# STM32F103ZET6.net
KiCad netlist of a schematic drawn in Altium Designer
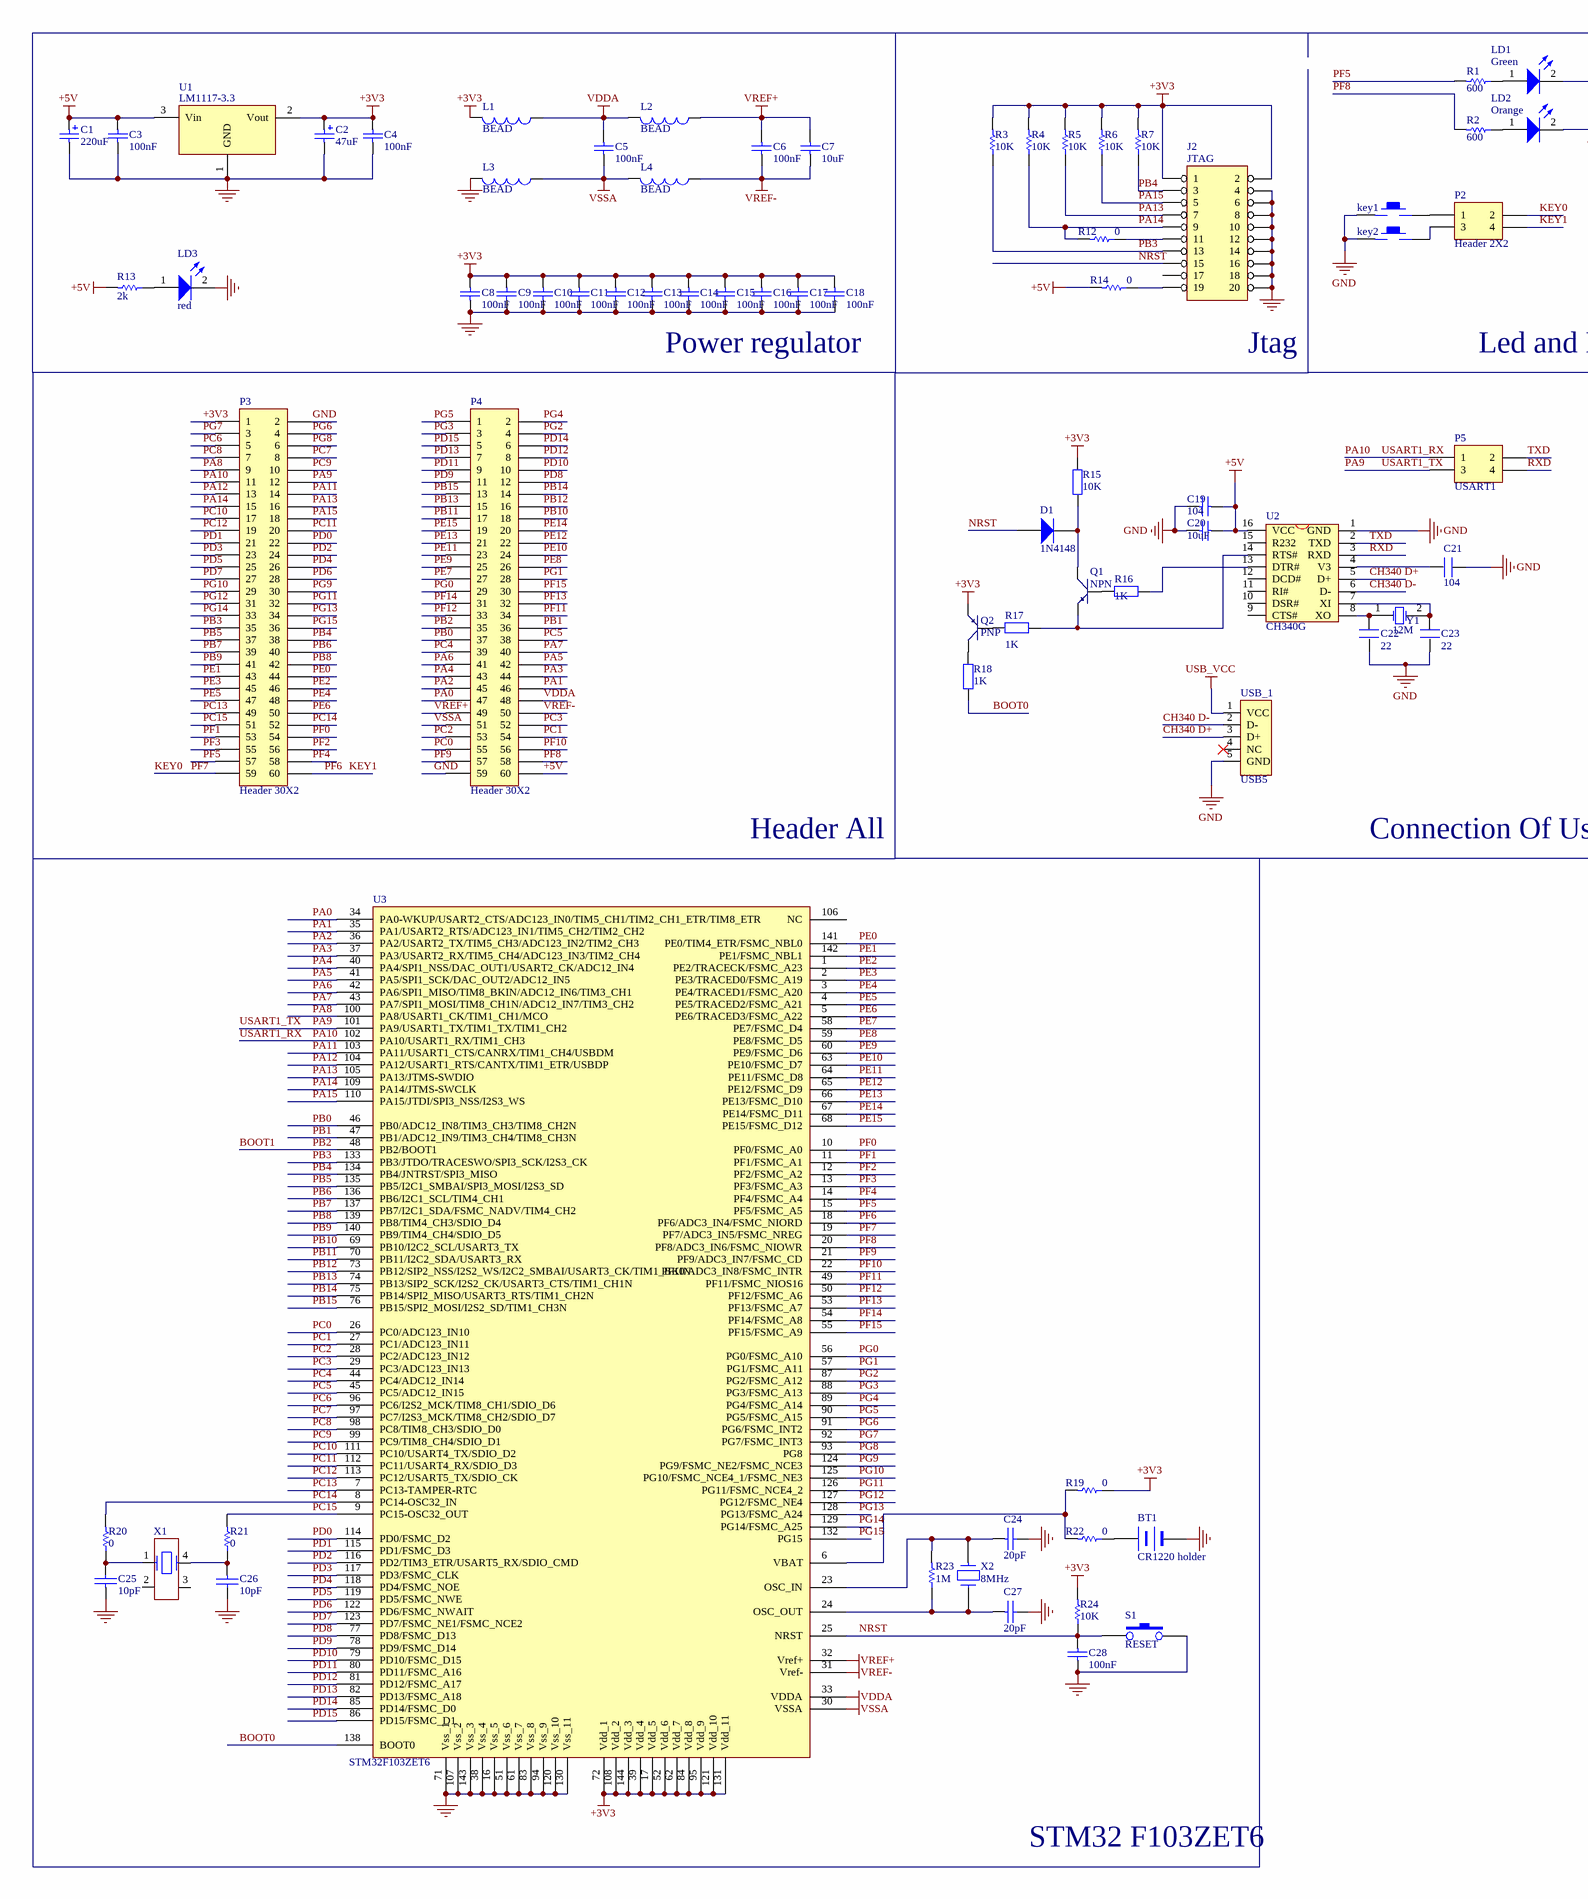
[diagram p0: STM32F103ZET6.SCHDOC, left]
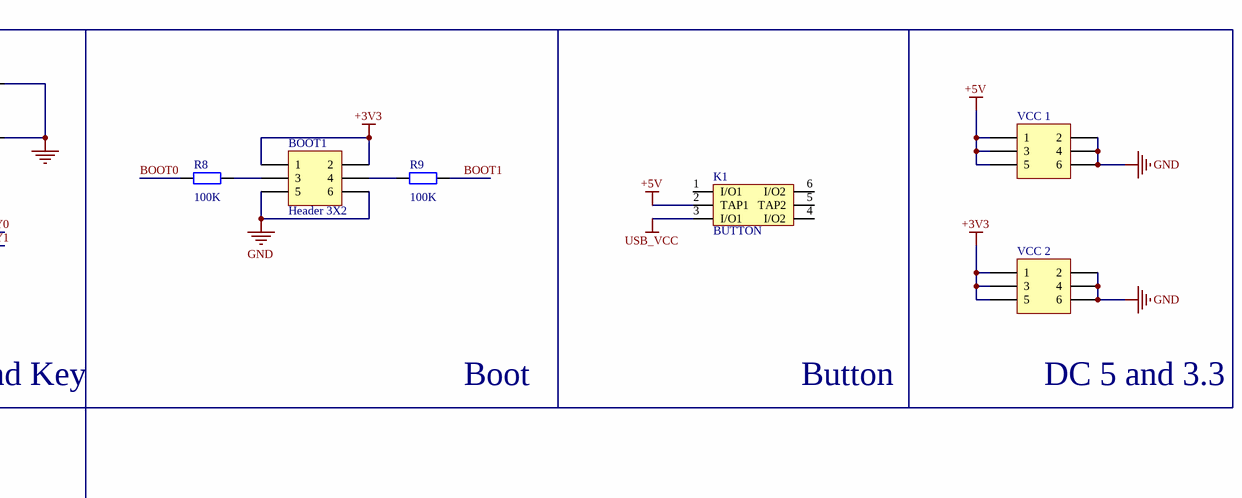
[diagram p1: STM32F103ZET6.SCHDOC, right]

(export (version "E")
  (design (tool "Eeschema 10.0.6"))
  (components
    (comp (ref "BOOT1")
      (value "Header 3X2")
      (footprint "HDR2X3")
      (description "Header, 3-Pin, Dual row")
      (fields (field (name "PUBLISHER") "*"))
      (libsource (lib "WARSHIP_SCH") (part "Header 3X2"))
    )
    (comp (ref "BT1")
      (value "CR1220 holder")
      (footprint "BAT")
      (description "Battery")
      (libsource (lib "*") (part "BATTERY"))
    )
    (comp (ref "C1")
      (value "220uF")
      (footprint "3528")
      (description "Polarized Capacitor (Radial)")
      (fields (field (name "PUBLISHER") "Altium Limited"))
      (libsource (lib "Miscellaneous Devices") (part "Cap Pol1"))
    )
    (comp (ref "C2")
      (value "47uF")
      (footprint "3528")
      (description "Polarized Capacitor (Radial)")
      (fields (field (name "PUBLISHER") "Altium Limited"))
      (libsource (lib "Miscellaneous Devices") (part "Cap Pol1"))
    )
    (comp (ref "C3")
      (value "100nF")
      (footprint "0603P")
      (description "Capacitor")
      (fields (field (name "PUBLISHER") "Altium Limited"))
      (libsource (lib "Miscellaneous Devices") (part "Cap"))
    )
    (comp (ref "C4")
      (value "100nF")
      (footprint "0603P")
      (description "Capacitor")
      (fields (field (name "PUBLISHER") "Altium Limited"))
      (libsource (lib "Miscellaneous Devices") (part "Cap"))
    )
    (comp (ref "C5")
      (value "100nF")
      (footprint "0603P")
      (description "Capacitor")
      (fields (field (name "PUBLISHER") "Altium Limited"))
      (libsource (lib "Miscellaneous Devices") (part "Cap"))
    )
    (comp (ref "C6")
      (value "100nF")
      (footprint "0603P")
      (description "Capacitor")
      (fields (field (name "PUBLISHER") "Altium Limited"))
      (libsource (lib "Miscellaneous Devices") (part "Cap"))
    )
    (comp (ref "C7")
      (value "10uF")
      (footprint "3528")
      (description "Capacitor")
      (fields (field (name "PUBLISHER") "Altium Limited"))
      (libsource (lib "Miscellaneous Devices") (part "Cap"))
    )
    (comp (ref "C8")
      (value "100nF")
      (footprint "0603P")
      (description "Capacitor")
      (fields (field (name "PUBLISHER") "Altium Limited"))
      (libsource (lib "Miscellaneous Devices") (part "CAP"))
    )
    (comp (ref "C9")
      (value "100nF")
      (footprint "0603P")
      (description "Capacitor")
      (fields (field (name "PUBLISHER") "Altium Limited"))
      (libsource (lib "Miscellaneous Devices") (part "CAP"))
    )
    (comp (ref "C10")
      (value "100nF")
      (footprint "0603P")
      (description "Capacitor")
      (fields (field (name "PUBLISHER") "Altium Limited"))
      (libsource (lib "Miscellaneous Devices") (part "CAP"))
    )
    (comp (ref "C11")
      (value "100nF")
      (footprint "0603P")
      (description "Capacitor")
      (fields (field (name "PUBLISHER") "Altium Limited"))
      (libsource (lib "Miscellaneous Devices") (part "CAP"))
    )
    (comp (ref "C12")
      (value "100nF")
      (footprint "0603P")
      (description "Capacitor")
      (fields (field (name "PUBLISHER") "Altium Limited"))
      (libsource (lib "Miscellaneous Devices") (part "CAP"))
    )
    (comp (ref "C13")
      (value "100nF")
      (footprint "0603P")
      (description "Capacitor")
      (fields (field (name "PUBLISHER") "Altium Limited"))
      (libsource (lib "Miscellaneous Devices") (part "CAP"))
    )
    (comp (ref "C14")
      (value "100nF")
      (footprint "0603P")
      (description "Capacitor")
      (fields (field (name "PUBLISHER") "Altium Limited"))
      (libsource (lib "Miscellaneous Devices") (part "CAP"))
    )
    (comp (ref "C15")
      (value "100nF")
      (footprint "0603P")
      (description "Capacitor")
      (fields (field (name "PUBLISHER") "Altium Limited"))
      (libsource (lib "Miscellaneous Devices") (part "CAP"))
    )
    (comp (ref "C16")
      (value "100nF")
      (footprint "0603P")
      (description "Capacitor")
      (fields (field (name "PUBLISHER") "Altium Limited"))
      (libsource (lib "Miscellaneous Devices") (part "CAP"))
    )
    (comp (ref "C17")
      (value "100nF")
      (footprint "0603P")
      (description "Capacitor")
      (fields (field (name "PUBLISHER") "Altium Limited"))
      (libsource (lib "Miscellaneous Devices") (part "CAP"))
    )
    (comp (ref "C18")
      (value "100nF")
      (footprint "0603P")
      (description "Capacitor")
      (fields (field (name "PUBLISHER") "Altium Limited"))
      (libsource (lib "Miscellaneous Devices") (part "CAP"))
    )
    (comp (ref "C19")
      (value "104")
      (footprint "0603P")
      (description "Capacitor")
      (fields (field (name "Comment") "Cap") (field (name "PUBLISHER") "Altium Limited"))
      (libsource (lib "Miscellaneous Devices") (part "Cap"))
    )
    (comp (ref "C20")
      (value "10uF")
      (footprint "0603P")
      (description "Capacitor")
      (fields (field (name "Comment") "Cap") (field (name "PUBLISHER") "Altium Limited"))
      (libsource (lib "Miscellaneous Devices") (part "Cap"))
    )
    (comp (ref "C21") (value "104") (footprint "0603P") (libsource (lib "WARSHIP_SCH") (part "C")))
    (comp (ref "C22") (value "22") (footprint "0603P") (libsource (lib "WARSHIP_SCH") (part "C")))
    (comp (ref "C23") (value "22") (footprint "0603P") (libsource (lib "WARSHIP_SCH") (part "C")))
    (comp (ref "C24")
      (value "20pF")
      (footprint "0603P")
      (description "Capacitor")
      (libsource (lib "*") (part "CAP"))
    )
    (comp (ref "C25")
      (value "10pF")
      (footprint "0603P")
      (description "Capacitor")
      (libsource (lib "") (part "CAP_1"))
    )
    (comp (ref "C26")
      (value "10pF")
      (footprint "0603P")
      (description "Capacitor")
      (libsource (lib "") (part "CAP_1"))
    )
    (comp (ref "C27")
      (value "20pF")
      (footprint "0603P")
      (description "Capacitor")
      (libsource (lib "*") (part "CAP"))
    )
    (comp (ref "C28")
      (value "100nF")
      (footprint "0603P")
      (description "Capacitor")
      (fields (field (name "PUBLISHER") "Altium Limited"))
      (libsource (lib "Miscellaneous Devices") (part "CAP"))
    )
    (comp (ref "D1")
      (value "1N4148")
      (footprint "DO-35")
      (description "High Conductance Fast Diode")
      (fields (field (name "PUBLISHER") "Altium Limited"))
      (libsource (lib "Miscellaneous Devices") (part "Diode 1N4148"))
    )
    (comp (ref "J2") (value "JTAG") (footprint "JTAG_20PIN") (libsource (lib "*") (part "HEADER 10X2")))
    (comp (ref "K1")
      (value "BUTTON")
      (footprint "BTN8.5*8.5")
      (libsource (lib "WARSHIP_SCH") (part "BUTTON"))
    )
    (comp (ref "key1") (value "KEY_M") (footprint "KEY_M") (libsource (lib "WARSHIP_SCH") (part "KEY_M")))
    (comp (ref "key2") (value "KEY_M") (footprint "KEY_M") (libsource (lib "WARSHIP_SCH") (part "KEY_M")))
    (comp (ref "L1")
      (value "BEAD")
      (footprint "0603P")
      (description "Inductor")
      (fields (field (name "PUBLISHER") "Altium Limited"))
      (libsource (lib "Miscellaneous Devices") (part "Inductor"))
    )
    (comp (ref "L2")
      (value "BEAD")
      (footprint "0603P")
      (description "Inductor")
      (fields (field (name "PUBLISHER") "Altium Limited"))
      (libsource (lib "Miscellaneous Devices") (part "Inductor"))
    )
    (comp (ref "L3")
      (value "BEAD")
      (footprint "0603P")
      (description "Inductor")
      (fields (field (name "PUBLISHER") "Altium Limited"))
      (libsource (lib "Miscellaneous Devices") (part "Inductor"))
    )
    (comp (ref "L4")
      (value "BEAD")
      (footprint "0603P")
      (description "Inductor")
      (fields (field (name "PUBLISHER") "Altium Limited"))
      (libsource (lib "Miscellaneous Devices") (part "Inductor"))
    )
    (comp (ref "LD1")
      (value "Green")
      (footprint "0603P")
      (description "Typical RED, GREEN, YELLOW, AMBER GaAs LED")
      (fields (field (name "PUBLISHER") "Altium Limited"))
      (libsource (lib "Miscellaneous Devices") (part "LED2"))
    )
    (comp (ref "LD2")
      (value "Orange")
      (footprint "0603P")
      (description "Typical RED, GREEN, YELLOW, AMBER GaAs LED")
      (fields (field (name "PUBLISHER") "Altium Limited"))
      (libsource (lib "Miscellaneous Devices") (part "LED2"))
    )
    (comp (ref "LD3")
      (value "red")
      (footprint "0603P")
      (description "Typical RED, GREEN, YELLOW, AMBER GaAs LED")
      (fields (field (name "PUBLISHER") "Altium Limited"))
      (libsource (lib "Miscellaneous Devices") (part "LED2"))
    )
    (comp (ref "P2")
      (value "Header 2X2")
      (footprint "HDR2X2")
      (description "Header, 2-Pin, Dual row")
      (fields (field (name "PUBLISHER") "*"))
      (libsource (lib "WARSHIP_SCH") (part "Header 2X2"))
    )
    (comp (ref "P3")
      (value "Header 30X2")
      (footprint "60pin")
      (description "Header, 30-Pin, Dual row")
      (fields (field (name "PUBLISHER") "Altium Limited"))
      (libsource (lib "Miscellaneous Connectors") (part "Header 30X2"))
    )
    (comp (ref "P4")
      (value "Header 30X2")
      (footprint "60pin")
      (description "Header, 30-Pin, Dual row")
      (fields (field (name "PUBLISHER") "Altium Limited"))
      (libsource (lib "Miscellaneous Connectors") (part "Header 30X2"))
    )
    (comp (ref "P5")
      (value "USART1")
      (footprint "HDR2X2")
      (description "Header, 2-Pin, Dual row")
      (fields (field (name "PUBLISHER") "*"))
      (libsource (lib "WARSHIP_SCH") (part "Header 2X2"))
    )
    (comp (ref "Q1")
      (value "NPN")
      (footprint "SOT-23R")
      (description "8050/BCW846/BCW847")
      (libsource (lib "WARSHIP_SCH") (part "NPN"))
    )
    (comp (ref "Q2")
      (value "PNP")
      (footprint "SOT-23R")
      (description "8550/BCW68")
      (libsource (lib "WARSHIP_SCH") (part "PNP"))
    )
    (comp (ref "R1")
      (value "600")
      (footprint "0603P")
      (description "Resistor")
      (fields (field (name "PUBLISHER") "Altium Limited"))
      (libsource (lib "Miscellaneous Devices") (part "Res1"))
    )
    (comp (ref "R2")
      (value "600")
      (footprint "0603P")
      (description "Resistor")
      (fields (field (name "PUBLISHER") "Altium Limited"))
      (libsource (lib "Miscellaneous Devices") (part "Res1"))
    )
    (comp (ref "R3")
      (value "10K")
      (footprint "0603P")
      (description "Resistor")
      (fields (field (name "PUBLISHER") "Altium Limited"))
      (libsource (lib "Miscellaneous Devices") (part "Res1"))
    )
    (comp (ref "R4")
      (value "10K")
      (footprint "0603P")
      (description "Resistor")
      (fields (field (name "PUBLISHER") "Altium Limited"))
      (libsource (lib "Miscellaneous Devices") (part "Res1"))
    )
    (comp (ref "R5")
      (value "10K")
      (footprint "0603P")
      (description "Resistor")
      (fields (field (name "PUBLISHER") "Altium Limited"))
      (libsource (lib "Miscellaneous Devices") (part "Res1"))
    )
    (comp (ref "R6")
      (value "10K")
      (footprint "0603P")
      (description "Resistor")
      (fields (field (name "PUBLISHER") "Altium Limited"))
      (libsource (lib "Miscellaneous Devices") (part "Res1"))
    )
    (comp (ref "R7")
      (value "10K")
      (footprint "0603P")
      (description "Resistor")
      (fields (field (name "PUBLISHER") "Altium Limited"))
      (libsource (lib "Miscellaneous Devices") (part "Res1"))
    )
    (comp (ref "R8")
      (value "100K")
      (footprint "0603P")
      (description "Resistor")
      (fields (field (name "Comment") "Res2") (field (name "PUBLISHER") "Altium Limited"))
      (libsource (lib "") (part "Res2_1"))
    )
    (comp (ref "R9")
      (value "100K")
      (footprint "0603P")
      (description "Resistor")
      (fields (field (name "Comment") "Res2") (field (name "PUBLISHER") "Altium Limited"))
      (libsource (lib "") (part "Res2_1"))
    )
    (comp (ref "R12")
      (value "0")
      (footprint "0603P")
      (description "Resistor")
      (fields (field (name "PUBLISHER") "Altium Limited"))
      (libsource (lib "Miscellaneous Devices") (part "Res1"))
    )
    (comp (ref "R13")
      (value "2k")
      (footprint "0603P")
      (description "Resistor")
      (fields (field (name "PUBLISHER") "Altium Limited"))
      (libsource (lib "Miscellaneous Devices") (part "res1"))
    )
    (comp (ref "R14")
      (value "0")
      (footprint "0603P")
      (description "Resistor")
      (fields (field (name "PUBLISHER") "Altium Limited"))
      (libsource (lib "Miscellaneous Devices") (part "Res1"))
    )
    (comp (ref "R15")
      (value "10K")
      (footprint "0603P")
      (description "Resistor")
      (fields (field (name "Comment") "Res2") (field (name "PUBLISHER") "Altium Limited"))
      (libsource (lib "Miscellaneous Devices") (part "Res2"))
    )
    (comp (ref "R16")
      (value "1K")
      (footprint "0603P")
      (description "Resistor")
      (fields (field (name "Comment") "Res2") (field (name "PUBLISHER") "Altium Limited"))
      (libsource (lib "") (part "Res2_1"))
    )
    (comp (ref "R17")
      (value "1K")
      (footprint "0603P")
      (description "Resistor")
      (fields (field (name "Comment") "Res2") (field (name "PUBLISHER") "Altium Limited"))
      (libsource (lib "") (part "Res2_1"))
    )
    (comp (ref "R18")
      (value "1K")
      (footprint "0603P")
      (description "Resistor")
      (fields (field (name "Comment") "Res2") (field (name "PUBLISHER") "Altium Limited"))
      (libsource (lib "Miscellaneous Devices") (part "Res2"))
    )
    (comp (ref "R19")
      (value "0")
      (footprint "0603P")
      (description "Resistor")
      (fields (field (name "PUBLISHER") "Altium Limited"))
      (libsource (lib "Miscellaneous Devices") (part "Res1"))
    )
    (comp (ref "R20")
      (value "0")
      (footprint "0603P")
      (description "Resistor")
      (fields (field (name "PUBLISHER") "Altium Limited"))
      (libsource (lib "Miscellaneous Devices") (part "Res1"))
    )
    (comp (ref "R21")
      (value "0")
      (footprint "0603P")
      (description "Resistor")
      (fields (field (name "PUBLISHER") "Altium Limited"))
      (libsource (lib "Miscellaneous Devices") (part "Res1"))
    )
    (comp (ref "R22")
      (value "0")
      (footprint "0603P")
      (description "Resistor")
      (fields (field (name "PUBLISHER") "Altium Limited"))
      (libsource (lib "Miscellaneous Devices") (part "Res1"))
    )
    (comp (ref "R23")
      (value "1M")
      (footprint "0603P")
      (description "Resistor")
      (fields (field (name "PUBLISHER") "Altium Limited"))
      (libsource (lib "Miscellaneous Devices") (part "Res1"))
    )
    (comp (ref "R24")
      (value "10K")
      (footprint "0603P")
      (description "Resistor")
      (fields (field (name "PUBLISHER") "Altium Limited"))
      (libsource (lib "Miscellaneous Devices") (part "res1"))
    )
    (comp (ref "S1") (value "RESET") (footprint "KEY_M") (libsource (lib "*") (part "SW-PB")))
    (comp (ref "U1") (value "LM1117-3.3") (footprint "1117") (libsource (lib "*") (part "VOLTREG1")))
    (comp (ref "U2")
      (value "CH340G")
      (footprint "SOP16M")
      (description "USB2UART")
      (libsource (lib "WARSHIP_SCH") (part "CH340G"))
    )
    (comp (ref "U3")
      (value "STM32F103ZET6")
      (footprint "TQFP144-B")
      (libsource (lib "STM32F103ZET6") (part "STM32F103ZET6"))
    )
    (comp (ref "USB_1")
      (value "USB5")
      (footprint "USB/SM0.8-6H5")
      (libsource (lib "WARSHIP_SCH") (part "USB5"))
    )
    (comp (ref "VCC 1")
      (value "Header 3X2")
      (footprint "HDR2X3")
      (description "Header, 3-Pin, Dual row")
      (fields (field (name "PUBLISHER") "*"))
      (libsource (lib "WARSHIP_SCH") (part "Header 3X2"))
    )
    (comp (ref "VCC 2")
      (value "Header 3X2")
      (footprint "HDR2X3")
      (description "Header, 3-Pin, Dual row")
      (fields (field (name "PUBLISHER") "*"))
      (libsource (lib "WARSHIP_SCH") (part "Header 3X2"))
    )
    (comp (ref "X1")
      (value "MC306-G-06Q-32.768 (manufacturer JFVNY)")
      (footprint "SM8")
      (libsource (lib "*") (part "MC306"))
    )
    (comp (ref "X2")
      (value "8MHz")
      (footprint "XTAL_16S")
      (description "Crystal")
      (libsource (lib "*") (part "CRYSTAL"))
    )
    (comp (ref "Y1")
      (value "12M")
      (footprint "XTAL_US")
      (description "Crystal Oscillator")
      (fields (field (name "PUBLISHER") "*"))
      (libsource (lib "WARSHIP_SCH") (part "XTAL"))
    )
  )
  (nets
    (net (code "1") (name "+3V3") (class "Default")
      (node (ref "BOOT1") (pin "1") (pinfunction "1_1") (pintype "passive"))
      (node (ref "BOOT1") (pin "2") (pinfunction "2_2") (pintype "passive"))
      (node (ref "C10") (pin "1") (pinfunction "1_1") (pintype "passive"))
      (node (ref "C11") (pin "1") (pinfunction "1_1") (pintype "passive"))
      (node (ref "C12") (pin "1") (pinfunction "1_1") (pintype "passive"))
      (node (ref "C13") (pin "1") (pinfunction "1_1") (pintype "passive"))
      (node (ref "C14") (pin "1") (pinfunction "1_1") (pintype "passive"))
      (node (ref "C15") (pin "1") (pinfunction "1_1") (pintype "passive"))
      (node (ref "C16") (pin "1") (pinfunction "1_1") (pintype "passive"))
      (node (ref "C17") (pin "1") (pinfunction "1_1") (pintype "passive"))
      (node (ref "C18") (pin "1") (pinfunction "1_1") (pintype "passive"))
      (node (ref "C2") (pin "1") (pinfunction "1_1") (pintype "passive"))
      (node (ref "C4") (pin "1") (pinfunction "1_1") (pintype "passive"))
      (node (ref "C8") (pin "1") (pinfunction "1_1") (pintype "passive"))
      (node (ref "C9") (pin "1") (pinfunction "1_1") (pintype "passive"))
      (node (ref "J2") (pin "1") (pinfunction "1_1") (pintype "passive"))
      (node (ref "J2") (pin "2") (pinfunction "2_2") (pintype "passive"))
      (node (ref "L1") (pin "2") (pinfunction "2_2") (pintype "passive"))
      (node (ref "P3") (pin "1") (pinfunction "1_1") (pintype "passive"))
      (node (ref "Q2") (pin "1") (pinfunction "E_1") (pintype "passive"))
      (node (ref "R15") (pin "2") (pinfunction "2_2") (pintype "passive"))
      (node (ref "R19") (pin "1") (pinfunction "1_1") (pintype "passive"))
      (node (ref "R24") (pin "2") (pinfunction "2_2") (pintype "passive"))
      (node (ref "R3") (pin "2") (pinfunction "2_2") (pintype "passive"))
      (node (ref "R4") (pin "2") (pinfunction "2_2") (pintype "passive"))
      (node (ref "R5") (pin "2") (pinfunction "2_2") (pintype "passive"))
      (node (ref "R6") (pin "2") (pinfunction "2_2") (pintype "passive"))
      (node (ref "R7") (pin "2") (pinfunction "2_2") (pintype "passive"))
      (node (ref "U1") (pin "2") (pinfunction "Vout_2") (pintype "passive"))
      (node (ref "U3") (pin "108") (pinfunction "Vdd_2_108") (pintype "passive"))
      (node (ref "U3") (pin "121") (pinfunction "Vdd_10_121") (pintype "passive"))
      (node (ref "U3") (pin "131") (pinfunction "Vdd_11_131") (pintype "passive"))
      (node (ref "U3") (pin "144") (pinfunction "Vdd_3_144") (pintype "passive"))
      (node (ref "U3") (pin "17") (pinfunction "Vdd_5_17") (pintype "passive"))
      (node (ref "U3") (pin "39") (pinfunction "Vdd_4_39") (pintype "passive"))
      (node (ref "U3") (pin "52") (pinfunction "Vdd_6_52") (pintype "passive"))
      (node (ref "U3") (pin "62") (pinfunction "Vdd_7_62") (pintype "passive"))
      (node (ref "U3") (pin "72") (pinfunction "Vdd_1_72") (pintype "passive"))
      (node (ref "U3") (pin "84") (pinfunction "Vdd_8_84") (pintype "passive"))
      (node (ref "U3") (pin "95") (pinfunction "Vdd_9_95") (pintype "passive"))
      (node (ref "VCC 2") (pin "1") (pinfunction "1_1") (pintype "passive"))
      (node (ref "VCC 2") (pin "3") (pinfunction "3_3") (pintype "passive"))
      (node (ref "VCC 2") (pin "5") (pinfunction "5_5") (pintype "passive"))
    )
    (net (code "2") (name "+5V") (class "Default")
      (node (ref "C1") (pin "1") (pinfunction "1_1") (pintype "passive"))
      (node (ref "C19") (pin "2") (pinfunction "2_2") (pintype "passive"))
      (node (ref "C20") (pin "2") (pinfunction "2_2") (pintype "passive"))
      (node (ref "C3") (pin "1") (pinfunction "1_1") (pintype "passive"))
      (node (ref "K1") (pin "2") (pinfunction "TAP1_2") (pintype "passive"))
      (node (ref "P4") (pin "60") (pinfunction "60_60") (pintype "passive"))
      (node (ref "R13") (pin "2") (pinfunction "2_2") (pintype "passive"))
      (node (ref "R14") (pin "2") (pinfunction "2_2") (pintype "passive"))
      (node (ref "U1") (pin "3") (pinfunction "Vin_3") (pintype "passive"))
      (node (ref "U2") (pin "16") (pinfunction "VCC_16") (pintype "passive"))
      (node (ref "VCC 1") (pin "1") (pinfunction "1_1") (pintype "passive"))
      (node (ref "VCC 1") (pin "3") (pinfunction "3_3") (pintype "passive"))
      (node (ref "VCC 1") (pin "5") (pinfunction "5_5") (pintype "passive"))
    )
    (net (code "3") (name "/BOOT0") (class "Default")
      (node (ref "R18") (pin "1") (pinfunction "1_1") (pintype "passive"))
      (node (ref "R8") (pin "1") (pinfunction "1_1") (pintype "passive"))
      (node (ref "U3") (pin "138") (pinfunction "BOOT0_138") (pintype "passive"))
    )
    (net (code "4") (name "/BOOT1") (class "Default")
      (node (ref "P4") (pin "35") (pinfunction "35_35") (pintype "passive"))
      (node (ref "R9") (pin "2") (pinfunction "2_2") (pintype "passive"))
      (node (ref "U3") (pin "48") (pinfunction "PB2/BOOT1_48") (pintype "passive"))
    )
    (net (code "5") (name "/CH340 D+") (class "Default")
      (node (ref "U2") (pin "5") (pinfunction "D+_5") (pintype "passive"))
      (node (ref "USB_1") (pin "3") (pinfunction "D+_3") (pintype "passive"))
    )
    (net (code "6") (name "/CH340 D-") (class "Default")
      (node (ref "U2") (pin "6") (pinfunction "D-_6") (pintype "passive"))
      (node (ref "USB_1") (pin "2") (pinfunction "D-_2") (pintype "passive"))
    )
    (net (code "7") (name "/KEY0") (class "Default")
      (node (ref "P2") (pin "2") (pinfunction "2_2") (pintype "passive"))
      (node (ref "P3") (pin "59") (pinfunction "59_59") (pintype "passive"))
      (node (ref "U3") (pin "19") (pinfunction "PF7/ADC3_IN5/FSMC_NREG_19") (pintype "passive"))
    )
    (net (code "8") (name "/KEY1") (class "Default")
      (node (ref "P2") (pin "4") (pinfunction "4_4") (pintype "passive"))
      (node (ref "P3") (pin "60") (pinfunction "60_60") (pintype "passive"))
      (node (ref "U3") (pin "18") (pinfunction "PF6/ADC3_IN4/FSMC_NIORD_18") (pintype "passive"))
    )
    (net (code "9") (name "/NRST") (class "Default")
      (node (ref "C28") (pin "2") (pinfunction "2_2") (pintype "passive"))
      (node (ref "D1") (pin "1") (pinfunction "A_1") (pintype "passive"))
      (node (ref "J2") (pin "15") (pinfunction "15_15") (pintype "passive"))
      (node (ref "R24") (pin "1") (pinfunction "1_1") (pintype "passive"))
      (node (ref "S1") (pin "1") (pinfunction "1_1") (pintype "passive"))
      (node (ref "U3") (pin "25") (pinfunction "NRST_25") (pintype "passive"))
    )
    (net (code "10") (name "/PA0") (class "Default")
      (node (ref "P4") (pin "47") (pinfunction "47_47") (pintype "passive"))
      (node (ref "U3") (pin "34") (pinfunction "PA0-WKUP/USART2_CTS/ADC123_IN0/TIM5_CH1/TIM2_CH1_ETR/TIM8_ETR_34") (pintype "passive"))
    )
    (net (code "11") (name "/PA1") (class "Default")
      (node (ref "P4") (pin "46") (pinfunction "46_46") (pintype "passive"))
      (node (ref "U3") (pin "35") (pinfunction "PA1/USART2_RTS/ADC123_IN1/TIM5_CH2/TIM2_CH2_35") (pintype "passive"))
    )
    (net (code "12") (name "/PA2") (class "Default")
      (node (ref "P4") (pin "45") (pinfunction "45_45") (pintype "passive"))
      (node (ref "U3") (pin "36") (pinfunction "PA2/USART2_TX/TIM5_CH3/ADC123_IN2/TIM2_CH3_36") (pintype "passive"))
    )
    (net (code "13") (name "/PA3") (class "Default")
      (node (ref "P4") (pin "44") (pinfunction "44_44") (pintype "passive"))
      (node (ref "U3") (pin "37") (pinfunction "PA3/USART2_RX/TIM5_CH4/ADC123_IN3/TIM2_CH4_37") (pintype "passive"))
    )
    (net (code "14") (name "/PA4") (class "Default")
      (node (ref "P4") (pin "43") (pinfunction "43_43") (pintype "passive"))
      (node (ref "U3") (pin "40") (pinfunction "PA4/SPI1_NSS/DAC_OUT1/USART2_CK/ADC12_IN4_40") (pintype "passive"))
    )
    (net (code "15") (name "/PA5") (class "Default")
      (node (ref "P4") (pin "42") (pinfunction "42_42") (pintype "passive"))
      (node (ref "U3") (pin "41") (pinfunction "PA5/SPI1_SCK/DAC_OUT2/ADC12_IN5_41") (pintype "passive"))
    )
    (net (code "16") (name "/PA6") (class "Default")
      (node (ref "P4") (pin "41") (pinfunction "41_41") (pintype "passive"))
      (node (ref "U3") (pin "42") (pinfunction "PA6/SPI1_MISO/TIM8_BKIN/ADC12_IN6/TIM3_CH1_42") (pintype "passive"))
    )
    (net (code "17") (name "/PA7") (class "Default")
      (node (ref "P4") (pin "40") (pinfunction "40_40") (pintype "passive"))
      (node (ref "U3") (pin "43") (pinfunction "PA7/SPI1_MOSI/TIM8_CH1N/ADC12_IN7/TIM3_CH2_43") (pintype "passive"))
    )
    (net (code "18") (name "/PA8") (class "Default")
      (node (ref "P3") (pin "9") (pinfunction "9_9") (pintype "passive"))
      (node (ref "U3") (pin "100") (pinfunction "PA8/USART1_CK/TIM1_CH1/MCO_100") (pintype "passive"))
    )
    (net (code "19") (name "/PA9") (class "Default")
      (node (ref "P3") (pin "12") (pinfunction "12_12") (pintype "passive"))
      (node (ref "P5") (pin "3") (pinfunction "3_3") (pintype "passive"))
      (node (ref "U3") (pin "101") (pinfunction "PA9/USART1_TX/TIM1_TX/TIM1_CH2_101") (pintype "passive"))
    )
    (net (code "20") (name "/PA10") (class "Default")
      (node (ref "P3") (pin "11") (pinfunction "11_11") (pintype "passive"))
      (node (ref "P5") (pin "1") (pinfunction "1_1") (pintype "passive"))
      (node (ref "U3") (pin "102") (pinfunction "PA10/USART1_RX/TIM1_CH3_102") (pintype "passive"))
    )
    (net (code "21") (name "/PA11") (class "Default")
      (node (ref "P3") (pin "14") (pinfunction "14_14") (pintype "passive"))
      (node (ref "U3") (pin "103") (pinfunction "PA11/USART1_CTS/CANRX/TIM1_CH4/USBDM_103") (pintype "passive"))
    )
    (net (code "22") (name "/PA12") (class "Default")
      (node (ref "P3") (pin "13") (pinfunction "13_13") (pintype "passive"))
      (node (ref "U3") (pin "104") (pinfunction "PA12/USART1_RTS/CANTX/TIM1_ETR/USBDP_104") (pintype "passive"))
    )
    (net (code "23") (name "/PA13") (class "Default")
      (node (ref "J2") (pin "7") (pinfunction "7_7") (pintype "passive"))
      (node (ref "P3") (pin "16") (pinfunction "16_16") (pintype "passive"))
      (node (ref "R5") (pin "1") (pinfunction "1_1") (pintype "passive"))
      (node (ref "U3") (pin "105") (pinfunction "PA13/JTMS-SWDIO_105") (pintype "passive"))
    )
    (net (code "24") (name "/PA14") (class "Default")
      (node (ref "J2") (pin "9") (pinfunction "9_9") (pintype "passive"))
      (node (ref "P3") (pin "15") (pinfunction "15_15") (pintype "passive"))
      (node (ref "R12") (pin "2") (pinfunction "2_2") (pintype "passive"))
      (node (ref "R4") (pin "1") (pinfunction "1_1") (pintype "passive"))
      (node (ref "U3") (pin "109") (pinfunction "PA14/JTMS-SWCLK_109") (pintype "passive"))
    )
    (net (code "25") (name "/PA15") (class "Default")
      (node (ref "J2") (pin "5") (pinfunction "5_5") (pintype "passive"))
      (node (ref "P3") (pin "18") (pinfunction "18_18") (pintype "passive"))
      (node (ref "R6") (pin "1") (pinfunction "1_1") (pintype "passive"))
      (node (ref "U3") (pin "110") (pinfunction "PA15/JTDI/SPI3_NSS/I2S3_WS_110") (pintype "passive"))
    )
    (net (code "26") (name "/PB0") (class "Default")
      (node (ref "P4") (pin "37") (pinfunction "37_37") (pintype "passive"))
      (node (ref "U3") (pin "46") (pinfunction "PB0/ADC12_IN8/TIM3_CH3/TIM8_CH2N_46") (pintype "passive"))
    )
    (net (code "27") (name "/PB1") (class "Default")
      (node (ref "P4") (pin "36") (pinfunction "36_36") (pintype "passive"))
      (node (ref "U3") (pin "47") (pinfunction "PB1/ADC12_IN9/TIM3_CH4/TIM8_CH3N_47") (pintype "passive"))
    )
    (net (code "28") (name "/PB3") (class "Default")
      (node (ref "J2") (pin "13") (pinfunction "13_13") (pintype "passive"))
      (node (ref "P3") (pin "35") (pinfunction "35_35") (pintype "passive"))
      (node (ref "R3") (pin "1") (pinfunction "1_1") (pintype "passive"))
      (node (ref "U3") (pin "133") (pinfunction "PB3/JTDO/TRACESWO/SPI3_SCK/I2S3_CK_133") (pintype "passive"))
    )
    (net (code "29") (name "/PB4") (class "Default")
      (node (ref "J2") (pin "3") (pinfunction "3_3") (pintype "passive"))
      (node (ref "P3") (pin "38") (pinfunction "38_38") (pintype "passive"))
      (node (ref "R7") (pin "1") (pinfunction "1_1") (pintype "passive"))
      (node (ref "U3") (pin "134") (pinfunction "PB4/JNTRST/SPI3_MISO_134") (pintype "passive"))
    )
    (net (code "30") (name "/PB5") (class "Default")
      (node (ref "P3") (pin "37") (pinfunction "37_37") (pintype "passive"))
      (node (ref "U3") (pin "135") (pinfunction "PB5/I2C1_SMBAI/SPI3_MOSI/I2S3_SD_135") (pintype "passive"))
    )
    (net (code "31") (name "/PB6") (class "Default")
      (node (ref "P3") (pin "40") (pinfunction "40_40") (pintype "passive"))
      (node (ref "U3") (pin "136") (pinfunction "PB6/I2C1_SCL/TIM4_CH1_136") (pintype "passive"))
    )
    (net (code "32") (name "/PB7") (class "Default")
      (node (ref "P3") (pin "39") (pinfunction "39_39") (pintype "passive"))
      (node (ref "U3") (pin "137") (pinfunction "PB7/I2C1_SDA/FSMC_NADV/TIM4_CH2_137") (pintype "passive"))
    )
    (net (code "33") (name "/PB8") (class "Default")
      (node (ref "P3") (pin "42") (pinfunction "42_42") (pintype "passive"))
      (node (ref "U3") (pin "139") (pinfunction "PB8/TIM4_CH3/SDIO_D4_139") (pintype "passive"))
    )
    (net (code "34") (name "/PB9") (class "Default")
      (node (ref "P3") (pin "41") (pinfunction "41_41") (pintype "passive"))
      (node (ref "U3") (pin "140") (pinfunction "PB9/TIM4_CH4/SDIO_D5_140") (pintype "passive"))
    )
    (net (code "35") (name "/PB10") (class "Default")
      (node (ref "P4") (pin "18") (pinfunction "18_18") (pintype "passive"))
      (node (ref "U3") (pin "69") (pinfunction "PB10/I2C2_SCL/USART3_TX_69") (pintype "passive"))
    )
    (net (code "36") (name "/PB11") (class "Default")
      (node (ref "P4") (pin "17") (pinfunction "17_17") (pintype "passive"))
      (node (ref "U3") (pin "70") (pinfunction "PB11/I2C2_SDA/USART3_RX_70") (pintype "passive"))
    )
    (net (code "37") (name "/PB12") (class "Default")
      (node (ref "P4") (pin "16") (pinfunction "16_16") (pintype "passive"))
      (node (ref "U3") (pin "73") (pinfunction "PB12/SIP2_NSS/I2S2_WS/I2C2_SMBAI/USART3_CK/TIM1_BKIN_73") (pintype "passive"))
    )
    (net (code "38") (name "/PB13") (class "Default")
      (node (ref "P4") (pin "15") (pinfunction "15_15") (pintype "passive"))
      (node (ref "U3") (pin "74") (pinfunction "PB13/SIP2_SCK/I2S2_CK/USART3_CTS/TIM1_CH1N_74") (pintype "passive"))
    )
    (net (code "39") (name "/PB14") (class "Default")
      (node (ref "P4") (pin "14") (pinfunction "14_14") (pintype "passive"))
      (node (ref "U3") (pin "75") (pinfunction "PB14/SPI2_MISO/USART3_RTS/TIM1_CH2N_75") (pintype "passive"))
    )
    (net (code "40") (name "/PB15") (class "Default")
      (node (ref "P4") (pin "13") (pinfunction "13_13") (pintype "passive"))
      (node (ref "U3") (pin "76") (pinfunction "PB15/SPI2_MOSI/I2S2_SD/TIM1_CH3N_76") (pintype "passive"))
    )
    (net (code "41") (name "/PC0") (class "Default")
      (node (ref "P4") (pin "55") (pinfunction "55_55") (pintype "passive"))
      (node (ref "U3") (pin "26") (pinfunction "PC0/ADC123_IN10_26") (pintype "passive"))
    )
    (net (code "42") (name "/PC1") (class "Default")
      (node (ref "P4") (pin "54") (pinfunction "54_54") (pintype "passive"))
      (node (ref "U3") (pin "27") (pinfunction "PC1/ADC123_IN11_27") (pintype "passive"))
    )
    (net (code "43") (name "/PC2") (class "Default")
      (node (ref "P4") (pin "53") (pinfunction "53_53") (pintype "passive"))
      (node (ref "U3") (pin "28") (pinfunction "PC2/ADC123_IN12_28") (pintype "passive"))
    )
    (net (code "44") (name "/PC3") (class "Default")
      (node (ref "P4") (pin "52") (pinfunction "52_52") (pintype "passive"))
      (node (ref "U3") (pin "29") (pinfunction "PC3/ADC123_IN13_29") (pintype "passive"))
    )
    (net (code "45") (name "/PC4") (class "Default")
      (node (ref "P4") (pin "39") (pinfunction "39_39") (pintype "passive"))
      (node (ref "U3") (pin "44") (pinfunction "PC4/ADC12_IN14_44") (pintype "passive"))
    )
    (net (code "46") (name "/PC5") (class "Default")
      (node (ref "P4") (pin "38") (pinfunction "38_38") (pintype "passive"))
      (node (ref "U3") (pin "45") (pinfunction "PC5/ADC12_IN15_45") (pintype "passive"))
    )
    (net (code "47") (name "/PC6") (class "Default")
      (node (ref "P3") (pin "5") (pinfunction "5_5") (pintype "passive"))
      (node (ref "U3") (pin "96") (pinfunction "PC6/I2S2_MCK/TIM8_CH1/SDIO_D6_96") (pintype "passive"))
    )
    (net (code "48") (name "/PC7") (class "Default")
      (node (ref "P3") (pin "8") (pinfunction "8_8") (pintype "passive"))
      (node (ref "U3") (pin "97") (pinfunction "PC7/I2S3_MCK/TIM8_CH2/SDIO_D7_97") (pintype "passive"))
    )
    (net (code "49") (name "/PC8") (class "Default")
      (node (ref "P3") (pin "7") (pinfunction "7_7") (pintype "passive"))
      (node (ref "U3") (pin "98") (pinfunction "PC8/TIM8_CH3/SDIO_D0_98") (pintype "passive"))
    )
    (net (code "50") (name "/PC9") (class "Default")
      (node (ref "P3") (pin "10") (pinfunction "10_10") (pintype "passive"))
      (node (ref "U3") (pin "99") (pinfunction "PC9/TIM8_CH4/SDIO_D1_99") (pintype "passive"))
    )
    (net (code "51") (name "/PC10") (class "Default")
      (node (ref "P3") (pin "17") (pinfunction "17_17") (pintype "passive"))
      (node (ref "U3") (pin "111") (pinfunction "PC10/USART4_TX/SDIO_D2_111") (pintype "passive"))
    )
    (net (code "52") (name "/PC11") (class "Default")
      (node (ref "P3") (pin "20") (pinfunction "20_20") (pintype "passive"))
      (node (ref "U3") (pin "112") (pinfunction "PC11/USART4_RX/SDIO_D3_112") (pintype "passive"))
    )
    (net (code "53") (name "/PC12") (class "Default")
      (node (ref "P3") (pin "19") (pinfunction "19_19") (pintype "passive"))
      (node (ref "U3") (pin "113") (pinfunction "PC12/USART5_TX/SDIO_CK_113") (pintype "passive"))
    )
    (net (code "54") (name "/PC13") (class "Default")
      (node (ref "P3") (pin "49") (pinfunction "49_49") (pintype "passive"))
      (node (ref "U3") (pin "7") (pinfunction "PC13-TAMPER-RTC_7") (pintype "passive"))
    )
    (net (code "55") (name "/PC14") (class "Default")
      (node (ref "P3") (pin "52") (pinfunction "52_52") (pintype "passive"))
      (node (ref "R20") (pin "2") (pinfunction "2_2") (pintype "passive"))
      (node (ref "U3") (pin "8") (pinfunction "PC14-OSC32_IN_8") (pintype "passive"))
    )
    (net (code "56") (name "/PC15") (class "Default")
      (node (ref "P3") (pin "51") (pinfunction "51_51") (pintype "passive"))
      (node (ref "R21") (pin "2") (pinfunction "2_2") (pintype "passive"))
      (node (ref "U3") (pin "9") (pinfunction "PC15-OSC32_OUT_9") (pintype "passive"))
    )
    (net (code "57") (name "/PD0") (class "Default")
      (node (ref "P3") (pin "22") (pinfunction "22_22") (pintype "passive"))
      (node (ref "U3") (pin "114") (pinfunction "PD0/FSMC_D2_114") (pintype "passive"))
    )
    (net (code "58") (name "/PD1") (class "Default")
      (node (ref "P3") (pin "21") (pinfunction "21_21") (pintype "passive"))
      (node (ref "U3") (pin "115") (pinfunction "PD1/FSMC_D3_115") (pintype "passive"))
    )
    (net (code "59") (name "/PD2") (class "Default")
      (node (ref "P3") (pin "24") (pinfunction "24_24") (pintype "passive"))
      (node (ref "U3") (pin "116") (pinfunction "PD2/TIM3_ETR/USART5_RX/SDIO_CMD_116") (pintype "passive"))
    )
    (net (code "60") (name "/PD3") (class "Default")
      (node (ref "P3") (pin "23") (pinfunction "23_23") (pintype "passive"))
      (node (ref "U3") (pin "117") (pinfunction "PD3/FSMC_CLK_117") (pintype "passive"))
    )
    (net (code "61") (name "/PD4") (class "Default")
      (node (ref "P3") (pin "26") (pinfunction "26_26") (pintype "passive"))
      (node (ref "U3") (pin "118") (pinfunction "PD4/FSMC_NOE_118") (pintype "passive"))
    )
    (net (code "62") (name "/PD5") (class "Default")
      (node (ref "P3") (pin "25") (pinfunction "25_25") (pintype "passive"))
      (node (ref "U3") (pin "119") (pinfunction "PD5/FSMC_NWE_119") (pintype "passive"))
    )
    (net (code "63") (name "/PD6") (class "Default")
      (node (ref "P3") (pin "28") (pinfunction "28_28") (pintype "passive"))
      (node (ref "U3") (pin "122") (pinfunction "PD6/FSMC_NWAIT_122") (pintype "passive"))
    )
    (net (code "64") (name "/PD7") (class "Default")
      (node (ref "P3") (pin "27") (pinfunction "27_27") (pintype "passive"))
      (node (ref "U3") (pin "123") (pinfunction "PD7/FSMC_NE1/FSMC_NCE2_123") (pintype "passive"))
    )
    (net (code "65") (name "/PD8") (class "Default")
      (node (ref "P4") (pin "12") (pinfunction "12_12") (pintype "passive"))
      (node (ref "U3") (pin "77") (pinfunction "PD8/FSMC_D13_77") (pintype "passive"))
    )
    (net (code "66") (name "/PD9") (class "Default")
      (node (ref "P4") (pin "11") (pinfunction "11_11") (pintype "passive"))
      (node (ref "U3") (pin "78") (pinfunction "PD9/FSMC_D14_78") (pintype "passive"))
    )
    (net (code "67") (name "/PD10") (class "Default")
      (node (ref "P4") (pin "10") (pinfunction "10_10") (pintype "passive"))
      (node (ref "U3") (pin "79") (pinfunction "PD10/FSMC_D15_79") (pintype "passive"))
    )
    (net (code "68") (name "/PD11") (class "Default")
      (node (ref "P4") (pin "9") (pinfunction "9_9") (pintype "passive"))
      (node (ref "U3") (pin "80") (pinfunction "PD11/FSMC_A16_80") (pintype "passive"))
    )
    (net (code "69") (name "/PD12") (class "Default")
      (node (ref "P4") (pin "8") (pinfunction "8_8") (pintype "passive"))
      (node (ref "U3") (pin "81") (pinfunction "PD12/FSMC_A17_81") (pintype "passive"))
    )
    (net (code "70") (name "/PD13") (class "Default")
      (node (ref "P4") (pin "7") (pinfunction "7_7") (pintype "passive"))
      (node (ref "U3") (pin "82") (pinfunction "PD13/FSMC_A18_82") (pintype "passive"))
    )
    (net (code "71") (name "/PD14") (class "Default")
      (node (ref "P4") (pin "6") (pinfunction "6_6") (pintype "passive"))
      (node (ref "U3") (pin "85") (pinfunction "PD14/FSMC_D0_85") (pintype "passive"))
    )
    (net (code "72") (name "/PD15") (class "Default")
      (node (ref "P4") (pin "5") (pinfunction "5_5") (pintype "passive"))
      (node (ref "U3") (pin "86") (pinfunction "PD15/FSMC_D1_86") (pintype "passive"))
    )
    (net (code "73") (name "/PE0") (class "Default")
      (node (ref "P3") (pin "44") (pinfunction "44_44") (pintype "passive"))
      (node (ref "U3") (pin "141") (pinfunction "PE0/TIM4_ETR/FSMC_NBL0_141") (pintype "passive"))
    )
    (net (code "74") (name "/PE1") (class "Default")
      (node (ref "P3") (pin "43") (pinfunction "43_43") (pintype "passive"))
      (node (ref "U3") (pin "142") (pinfunction "PE1/FSMC_NBL1_142") (pintype "passive"))
    )
    (net (code "75") (name "/PE2") (class "Default")
      (node (ref "P3") (pin "46") (pinfunction "46_46") (pintype "passive"))
      (node (ref "U3") (pin "1") (pinfunction "PE2/TRACECK/FSMC_A23_1") (pintype "passive"))
    )
    (net (code "76") (name "/PE3") (class "Default")
      (node (ref "P3") (pin "45") (pinfunction "45_45") (pintype "passive"))
      (node (ref "U3") (pin "2") (pinfunction "PE3/TRACED0/FSMC_A19_2") (pintype "passive"))
    )
    (net (code "77") (name "/PE4") (class "Default")
      (node (ref "P3") (pin "48") (pinfunction "48_48") (pintype "passive"))
      (node (ref "U3") (pin "3") (pinfunction "PE4/TRACED1/FSMC_A20_3") (pintype "passive"))
    )
    (net (code "78") (name "/PE5") (class "Default")
      (node (ref "P3") (pin "47") (pinfunction "47_47") (pintype "passive"))
      (node (ref "U3") (pin "4") (pinfunction "PE5/TRACED2/FSMC_A21_4") (pintype "passive"))
    )
    (net (code "79") (name "/PE6") (class "Default")
      (node (ref "P3") (pin "50") (pinfunction "50_50") (pintype "passive"))
      (node (ref "U3") (pin "5") (pinfunction "PE6/TRACED3/FSMC_A22_5") (pintype "passive"))
    )
    (net (code "80") (name "/PE7") (class "Default")
      (node (ref "P4") (pin "27") (pinfunction "27_27") (pintype "passive"))
      (node (ref "U3") (pin "58") (pinfunction "PE7/FSMC_D4_58") (pintype "passive"))
    )
    (net (code "81") (name "/PE8") (class "Default")
      (node (ref "P4") (pin "26") (pinfunction "26_26") (pintype "passive"))
      (node (ref "U3") (pin "59") (pinfunction "PE8/FSMC_D5_59") (pintype "passive"))
    )
    (net (code "82") (name "/PE9") (class "Default")
      (node (ref "P4") (pin "25") (pinfunction "25_25") (pintype "passive"))
      (node (ref "U3") (pin "60") (pinfunction "PE9/FSMC_D6_60") (pintype "passive"))
    )
    (net (code "83") (name "/PE10") (class "Default")
      (node (ref "P4") (pin "24") (pinfunction "24_24") (pintype "passive"))
      (node (ref "U3") (pin "63") (pinfunction "PE10/FSMC_D7_63") (pintype "passive"))
    )
    (net (code "84") (name "/PE11") (class "Default")
      (node (ref "P4") (pin "23") (pinfunction "23_23") (pintype "passive"))
      (node (ref "U3") (pin "64") (pinfunction "PE11/FSMC_D8_64") (pintype "passive"))
    )
    (net (code "85") (name "/PE12") (class "Default")
      (node (ref "P4") (pin "22") (pinfunction "22_22") (pintype "passive"))
      (node (ref "U3") (pin "65") (pinfunction "PE12/FSMC_D9_65") (pintype "passive"))
    )
    (net (code "86") (name "/PE13") (class "Default")
      (node (ref "P4") (pin "21") (pinfunction "21_21") (pintype "passive"))
      (node (ref "U3") (pin "66") (pinfunction "PE13/FSMC_D10_66") (pintype "passive"))
    )
    (net (code "87") (name "/PE14") (class "Default")
      (node (ref "P4") (pin "20") (pinfunction "20_20") (pintype "passive"))
      (node (ref "U3") (pin "67") (pinfunction "PE14/FSMC_D11_67") (pintype "passive"))
    )
    (net (code "88") (name "/PE15") (class "Default")
      (node (ref "P4") (pin "19") (pinfunction "19_19") (pintype "passive"))
      (node (ref "U3") (pin "68") (pinfunction "PE15/FSMC_D12_68") (pintype "passive"))
    )
    (net (code "89") (name "/PF0") (class "Default")
      (node (ref "P3") (pin "54") (pinfunction "54_54") (pintype "passive"))
      (node (ref "U3") (pin "10") (pinfunction "PF0/FSMC_A0_10") (pintype "passive"))
    )
    (net (code "90") (name "/PF1") (class "Default")
      (node (ref "P3") (pin "53") (pinfunction "53_53") (pintype "passive"))
      (node (ref "U3") (pin "11") (pinfunction "PF1/FSMC_A1_11") (pintype "passive"))
    )
    (net (code "91") (name "/PF2") (class "Default")
      (node (ref "P3") (pin "56") (pinfunction "56_56") (pintype "passive"))
      (node (ref "U3") (pin "12") (pinfunction "PF2/FSMC_A2_12") (pintype "passive"))
    )
    (net (code "92") (name "/PF3") (class "Default")
      (node (ref "P3") (pin "55") (pinfunction "55_55") (pintype "passive"))
      (node (ref "U3") (pin "13") (pinfunction "PF3/FSMC_A3_13") (pintype "passive"))
    )
    (net (code "93") (name "/PF4") (class "Default")
      (node (ref "P3") (pin "58") (pinfunction "58_58") (pintype "passive"))
      (node (ref "U3") (pin "14") (pinfunction "PF4/FSMC_A4_14") (pintype "passive"))
    )
    (net (code "94") (name "/PF5") (class "Default")
      (node (ref "P3") (pin "57") (pinfunction "57_57") (pintype "passive"))
      (node (ref "R1") (pin "2") (pinfunction "2_2") (pintype "passive"))
      (node (ref "U3") (pin "15") (pinfunction "PF5/FSMC_A5_15") (pintype "passive"))
    )
    (net (code "95") (name "/PF8") (class "Default")
      (node (ref "P4") (pin "58") (pinfunction "58_58") (pintype "passive"))
      (node (ref "R2") (pin "2") (pinfunction "2_2") (pintype "passive"))
      (node (ref "U3") (pin "20") (pinfunction "PF8/ADC3_IN6/FSMC_NIOWR_20") (pintype "passive"))
    )
    (net (code "96") (name "/PF9") (class "Default")
      (node (ref "P4") (pin "57") (pinfunction "57_57") (pintype "passive"))
      (node (ref "U3") (pin "21") (pinfunction "PF9/ADC3_IN7/FSMC_CD_21") (pintype "passive"))
    )
    (net (code "97") (name "/PF10") (class "Default")
      (node (ref "P4") (pin "56") (pinfunction "56_56") (pintype "passive"))
      (node (ref "U3") (pin "22") (pinfunction "PF10/ADC3_IN8/FSMC_INTR_22") (pintype "passive"))
    )
    (net (code "98") (name "/PF11") (class "Default")
      (node (ref "P4") (pin "34") (pinfunction "34_34") (pintype "passive"))
      (node (ref "U3") (pin "49") (pinfunction "PF11/FSMC_NIOS16_49") (pintype "passive"))
    )
    (net (code "99") (name "/PF12") (class "Default")
      (node (ref "P4") (pin "33") (pinfunction "33_33") (pintype "passive"))
      (node (ref "U3") (pin "50") (pinfunction "PF12/FSMC_A6_50") (pintype "passive"))
    )
    (net (code "100") (name "/PF13") (class "Default")
      (node (ref "P4") (pin "32") (pinfunction "32_32") (pintype "passive"))
      (node (ref "U3") (pin "53") (pinfunction "PF13/FSMC_A7_53") (pintype "passive"))
    )
    (net (code "101") (name "/PF14") (class "Default")
      (node (ref "P4") (pin "31") (pinfunction "31_31") (pintype "passive"))
      (node (ref "U3") (pin "54") (pinfunction "PF14/FSMC_A8_54") (pintype "passive"))
    )
    (net (code "102") (name "/PF15") (class "Default")
      (node (ref "P4") (pin "30") (pinfunction "30_30") (pintype "passive"))
      (node (ref "U3") (pin "55") (pinfunction "PF15/FSMC_A9_55") (pintype "passive"))
    )
    (net (code "103") (name "/PG0") (class "Default")
      (node (ref "P4") (pin "29") (pinfunction "29_29") (pintype "passive"))
      (node (ref "U3") (pin "56") (pinfunction "PG0/FSMC_A10_56") (pintype "passive"))
    )
    (net (code "104") (name "/PG1") (class "Default")
      (node (ref "P4") (pin "28") (pinfunction "28_28") (pintype "passive"))
      (node (ref "U3") (pin "57") (pinfunction "PG1/FSMC_A11_57") (pintype "passive"))
    )
    (net (code "105") (name "/PG2") (class "Default")
      (node (ref "P4") (pin "4") (pinfunction "4_4") (pintype "passive"))
      (node (ref "U3") (pin "87") (pinfunction "PG2/FSMC_A12_87") (pintype "passive"))
    )
    (net (code "106") (name "/PG3") (class "Default")
      (node (ref "P4") (pin "3") (pinfunction "3_3") (pintype "passive"))
      (node (ref "U3") (pin "88") (pinfunction "PG3/FSMC_A13_88") (pintype "passive"))
    )
    (net (code "107") (name "/PG4") (class "Default")
      (node (ref "P4") (pin "2") (pinfunction "2_2") (pintype "passive"))
      (node (ref "U3") (pin "89") (pinfunction "PG4/FSMC_A14_89") (pintype "passive"))
    )
    (net (code "108") (name "/PG5") (class "Default")
      (node (ref "P4") (pin "1") (pinfunction "1_1") (pintype "passive"))
      (node (ref "U3") (pin "90") (pinfunction "PG5/FSMC_A15_90") (pintype "passive"))
    )
    (net (code "109") (name "/PG6") (class "Default")
      (node (ref "P3") (pin "4") (pinfunction "4_4") (pintype "passive"))
      (node (ref "U3") (pin "91") (pinfunction "PG6/FSMC_INT2_91") (pintype "passive"))
    )
    (net (code "110") (name "/PG7") (class "Default")
      (node (ref "P3") (pin "3") (pinfunction "3_3") (pintype "passive"))
      (node (ref "U3") (pin "92") (pinfunction "PG7/FSMC_INT3_92") (pintype "passive"))
    )
    (net (code "111") (name "/PG8") (class "Default")
      (node (ref "P3") (pin "6") (pinfunction "6_6") (pintype "passive"))
      (node (ref "U3") (pin "93") (pinfunction "PG8_93") (pintype "passive"))
    )
    (net (code "112") (name "/PG9") (class "Default")
      (node (ref "P3") (pin "30") (pinfunction "30_30") (pintype "passive"))
      (node (ref "U3") (pin "124") (pinfunction "PG9/FSMC_NE2/FSMC_NCE3_124") (pintype "passive"))
    )
    (net (code "113") (name "/PG10") (class "Default")
      (node (ref "P3") (pin "29") (pinfunction "29_29") (pintype "passive"))
      (node (ref "U3") (pin "125") (pinfunction "PG10/FSMC_NCE4_1/FSMC_NE3_125") (pintype "passive"))
    )
    (net (code "114") (name "/PG11") (class "Default")
      (node (ref "P3") (pin "32") (pinfunction "32_32") (pintype "passive"))
      (node (ref "U3") (pin "126") (pinfunction "PG11/FSMC_NCE4_2_126") (pintype "passive"))
    )
    (net (code "115") (name "/PG12") (class "Default")
      (node (ref "P3") (pin "31") (pinfunction "31_31") (pintype "passive"))
      (node (ref "U3") (pin "127") (pinfunction "PG12/FSMC_NE4_127") (pintype "passive"))
    )
    (net (code "116") (name "/PG13") (class "Default")
      (node (ref "P3") (pin "34") (pinfunction "34_34") (pintype "passive"))
      (node (ref "U3") (pin "128") (pinfunction "PG13/FSMC_A24_128") (pintype "passive"))
    )
    (net (code "117") (name "/PG14") (class "Default")
      (node (ref "P3") (pin "33") (pinfunction "33_33") (pintype "passive"))
      (node (ref "U3") (pin "129") (pinfunction "PG14/FSMC_A25_129") (pintype "passive"))
    )
    (net (code "118") (name "/PG15") (class "Default")
      (node (ref "P3") (pin "36") (pinfunction "36_36") (pintype "passive"))
      (node (ref "U3") (pin "132") (pinfunction "PG15_132") (pintype "passive"))
    )
    (net (code "119") (name "/RXD") (class "Default")
      (node (ref "P5") (pin "4") (pinfunction "4_4") (pintype "passive"))
      (node (ref "U2") (pin "3") (pinfunction "RXD_3") (pintype "passive"))
    )
    (net (code "120") (name "/TXD") (class "Default")
      (node (ref "P5") (pin "2") (pinfunction "2_2") (pintype "passive"))
      (node (ref "U2") (pin "2") (pinfunction "TXD_2") (pintype "passive"))
    )
    (net (code "121") (name "GND") (class "Default")
      (node (ref "BOOT1") (pin "5") (pinfunction "5_5") (pintype "passive"))
      (node (ref "BOOT1") (pin "6") (pinfunction "6_6") (pintype "passive"))
      (node (ref "BT1") (pin "2") (pinfunction "-_2") (pintype "passive"))
      (node (ref "C1") (pin "2") (pinfunction "2_2") (pintype "passive"))
      (node (ref "C10") (pin "2") (pinfunction "2_2") (pintype "passive"))
      (node (ref "C11") (pin "2") (pinfunction "2_2") (pintype "passive"))
      (node (ref "C12") (pin "2") (pinfunction "2_2") (pintype "passive"))
      (node (ref "C13") (pin "2") (pinfunction "2_2") (pintype "passive"))
      (node (ref "C14") (pin "2") (pinfunction "2_2") (pintype "passive"))
      (node (ref "C15") (pin "2") (pinfunction "2_2") (pintype "passive"))
      (node (ref "C16") (pin "2") (pinfunction "2_2") (pintype "passive"))
      (node (ref "C17") (pin "2") (pinfunction "2_2") (pintype "passive"))
      (node (ref "C18") (pin "2") (pinfunction "2_2") (pintype "passive"))
      (node (ref "C19") (pin "1") (pinfunction "1_1") (pintype "passive"))
      (node (ref "C2") (pin "2") (pinfunction "2_2") (pintype "passive"))
      (node (ref "C20") (pin "1") (pinfunction "1_1") (pintype "passive"))
      (node (ref "C21") (pin "1") (pintype "passive"))
      (node (ref "C22") (pin "1") (pintype "passive"))
      (node (ref "C23") (pin "1") (pintype "passive"))
      (node (ref "C24") (pin "2") (pinfunction "2_2") (pintype "passive"))
      (node (ref "C25") (pin "1") (pinfunction "1_1") (pintype "passive"))
      (node (ref "C26") (pin "2") (pinfunction "2_2") (pintype "passive"))
      (node (ref "C27") (pin "2") (pinfunction "2_2") (pintype "passive"))
      (node (ref "C28") (pin "1") (pinfunction "1_1") (pintype "passive"))
      (node (ref "C3") (pin "2") (pinfunction "2_2") (pintype "passive"))
      (node (ref "C4") (pin "2") (pinfunction "2_2") (pintype "passive"))
      (node (ref "C8") (pin "2") (pinfunction "2_2") (pintype "passive"))
      (node (ref "C9") (pin "2") (pinfunction "2_2") (pintype "passive"))
      (node (ref "J2") (pin "10") (pinfunction "10_10") (pintype "passive"))
      (node (ref "J2") (pin "12") (pinfunction "12_12") (pintype "passive"))
      (node (ref "J2") (pin "14") (pinfunction "14_14") (pintype "passive"))
      (node (ref "J2") (pin "16") (pinfunction "16_16") (pintype "passive"))
      (node (ref "J2") (pin "18") (pinfunction "18_18") (pintype "passive"))
      (node (ref "J2") (pin "20") (pinfunction "20_20") (pintype "passive"))
      (node (ref "J2") (pin "4") (pinfunction "4_4") (pintype "passive"))
      (node (ref "J2") (pin "6") (pinfunction "6_6") (pintype "passive"))
      (node (ref "J2") (pin "8") (pinfunction "8_8") (pintype "passive"))
      (node (ref "L3") (pin "2") (pinfunction "2_2") (pintype "passive"))
      (node (ref "LD1") (pin "2") (pinfunction "K_2") (pintype "passive"))
      (node (ref "LD2") (pin "2") (pinfunction "K_2") (pintype "passive"))
      (node (ref "LD3") (pin "2") (pinfunction "K_2") (pintype "passive"))
      (node (ref "P3") (pin "2") (pinfunction "2_2") (pintype "passive"))
      (node (ref "P4") (pin "59") (pinfunction "59_59") (pintype "passive"))
      (node (ref "S1") (pin "2") (pinfunction "2_2") (pintype "passive"))
      (node (ref "U1") (pin "1") (pinfunction "GND_1") (pintype "passive"))
      (node (ref "U2") (pin "1") (pinfunction "GND_1") (pintype "passive"))
      (node (ref "U3") (pin "107") (pinfunction "Vss_2_107") (pintype "passive"))
      (node (ref "U3") (pin "120") (pinfunction "Vss_10_120") (pintype "passive"))
      (node (ref "U3") (pin "130") (pinfunction "Vss_11_130") (pintype "passive"))
      (node (ref "U3") (pin "143") (pinfunction "Vss_3_143") (pintype "passive"))
      (node (ref "U3") (pin "16") (pinfunction "Vss_5_16") (pintype "passive"))
      (node (ref "U3") (pin "38") (pinfunction "Vss_4_38") (pintype "passive"))
      (node (ref "U3") (pin "51") (pinfunction "Vss_6_51") (pintype "passive"))
      (node (ref "U3") (pin "61") (pinfunction "Vss_7_61") (pintype "passive"))
      (node (ref "U3") (pin "71") (pinfunction "Vss_1_71") (pintype "passive"))
      (node (ref "U3") (pin "83") (pinfunction "Vss_8_83") (pintype "passive"))
      (node (ref "U3") (pin "94") (pinfunction "Vss_9_94") (pintype "passive"))
      (node (ref "USB_1") (pin "5") (pinfunction "GND_5") (pintype "passive"))
      (node (ref "VCC 1") (pin "2") (pinfunction "2_2") (pintype "passive"))
      (node (ref "VCC 1") (pin "4") (pinfunction "4_4") (pintype "passive"))
      (node (ref "VCC 1") (pin "6") (pinfunction "6_6") (pintype "passive"))
      (node (ref "VCC 2") (pin "2") (pinfunction "2_2") (pintype "passive"))
      (node (ref "VCC 2") (pin "4") (pinfunction "4_4") (pintype "passive"))
      (node (ref "VCC 2") (pin "6") (pinfunction "6_6") (pintype "passive"))
      (node (ref "key1") (pin "1") (pinfunction "1_1") (pintype "passive"))
      (node (ref "key2") (pin "1") (pinfunction "1_1") (pintype "passive"))
    )
    (net (code "122") (name "Net-(BOOT1-Pad3)") (class "Default")
      (node (ref "BOOT1") (pin "3") (pinfunction "3_3") (pintype "passive"))
      (node (ref "R8") (pin "2") (pinfunction "2_2") (pintype "passive"))
    )
    (net (code "123") (name "Net-(BOOT1-Pad4)") (class "Default")
      (node (ref "BOOT1") (pin "4") (pinfunction "4_4") (pintype "passive"))
      (node (ref "R9") (pin "1") (pinfunction "1_1") (pintype "passive"))
    )
    (net (code "124") (name "Net-(BT1-+)") (class "Default")
      (node (ref "BT1") (pin "1") (pinfunction "+_1") (pintype "passive"))
      (node (ref "R22") (pin "1") (pinfunction "1_1") (pintype "passive"))
    )
    (net (code "125") (name "Net-(C25-Pad2)") (class "Default")
      (node (ref "C25") (pin "2") (pinfunction "2_2") (pintype "passive"))
      (node (ref "R20") (pin "1") (pinfunction "1_1") (pintype "passive"))
      (node (ref "X1") (pin "1") (pinfunction "1_1") (pintype "passive"))
    )
    (net (code "126") (name "Net-(C26-Pad1)") (class "Default")
      (node (ref "C26") (pin "1") (pinfunction "1_1") (pintype "passive"))
      (node (ref "R21") (pin "1") (pinfunction "1_1") (pintype "passive"))
      (node (ref "X1") (pin "4") (pinfunction "4_4") (pintype "passive"))
    )
    (net (code "127") (name "Net-(D1-K)") (class "Default")
      (node (ref "D1") (pin "2") (pinfunction "K_2") (pintype "passive"))
      (node (ref "Q1") (pin "3") (pinfunction "C_3") (pintype "passive"))
      (node (ref "R15") (pin "1") (pinfunction "1_1") (pintype "passive"))
    )
    (net (code "128") (name "Net-(J2-Pad11)") (class "Default")
      (node (ref "J2") (pin "11") (pinfunction "11_11") (pintype "passive"))
      (node (ref "R12") (pin "1") (pinfunction "1_1") (pintype "passive"))
    )
    (net (code "129") (name "Net-(J2-Pad19)") (class "Default")
      (node (ref "J2") (pin "19") (pinfunction "19_19") (pintype "passive"))
      (node (ref "R14") (pin "1") (pinfunction "1_1") (pintype "passive"))
    )
    (net (code "130") (name "Net-(LD1-A)") (class "Default")
      (node (ref "LD1") (pin "1") (pinfunction "A_1") (pintype "passive"))
      (node (ref "R1") (pin "1") (pinfunction "1_1") (pintype "passive"))
    )
    (net (code "131") (name "Net-(LD2-A)") (class "Default")
      (node (ref "LD2") (pin "1") (pinfunction "A_1") (pintype "passive"))
      (node (ref "R2") (pin "1") (pinfunction "1_1") (pintype "passive"))
    )
    (net (code "132") (name "Net-(LD3-A)") (class "Default")
      (node (ref "LD3") (pin "1") (pinfunction "A_1") (pintype "passive"))
      (node (ref "R13") (pin "1") (pinfunction "1_1") (pintype "passive"))
    )
    (net (code "133") (name "Net-(P2-Pad1)") (class "Default")
      (node (ref "P2") (pin "1") (pinfunction "1_1") (pintype "passive"))
      (node (ref "key1") (pin "2") (pinfunction "2_2") (pintype "passive"))
    )
    (net (code "134") (name "Net-(P2-Pad3)") (class "Default")
      (node (ref "P2") (pin "3") (pinfunction "3_3") (pintype "passive"))
      (node (ref "key2") (pin "2") (pinfunction "2_2") (pintype "passive"))
    )
    (net (code "135") (name "Net-(Q1-B)") (class "Default")
      (node (ref "Q1") (pin "2") (pinfunction "B_2") (pintype "passive"))
      (node (ref "R16") (pin "1") (pinfunction "1_1") (pintype "passive"))
    )
    (net (code "136") (name "Net-(Q1-E)") (class "Default")
      (node (ref "Q1") (pin "1") (pinfunction "E_1") (pintype "passive"))
      (node (ref "R17") (pin "2") (pinfunction "2_2") (pintype "passive"))
      (node (ref "U2") (pin "14") (pinfunction "RTS#_14") (pintype "passive"))
    )
    (net (code "137") (name "Net-(Q2-B)") (class "Default")
      (node (ref "Q2") (pin "2") (pinfunction "B_2") (pintype "passive"))
      (node (ref "R17") (pin "1") (pinfunction "1_1") (pintype "passive"))
    )
    (net (code "138") (name "Net-(Q2-C)") (class "Default")
      (node (ref "Q2") (pin "3") (pinfunction "C_3") (pintype "passive"))
      (node (ref "R18") (pin "2") (pinfunction "2_2") (pintype "passive"))
    )
    (net (code "139") (name "Net-(U2-DTR#)") (class "Default")
      (node (ref "R16") (pin "2") (pinfunction "2_2") (pintype "passive"))
      (node (ref "U2") (pin "13") (pinfunction "DTR#_13") (pintype "passive"))
    )
    (net (code "140") (name "Net-(U2-V3)") (class "Default")
      (node (ref "C21") (pin "2") (pintype "passive"))
      (node (ref "U2") (pin "4") (pinfunction "V3_4") (pintype "passive"))
    )
    (net (code "141") (name "Net-(U2-XI)") (class "Default")
      (node (ref "C23") (pin "2") (pintype "passive"))
      (node (ref "U2") (pin "7") (pinfunction "XI_7") (pintype "passive"))
      (node (ref "Y1") (pin "2") (pinfunction "OSC2_2") (pintype "passive"))
    )
    (net (code "142") (name "Net-(U2-XO)") (class "Default")
      (node (ref "C22") (pin "2") (pintype "passive"))
      (node (ref "U2") (pin "8") (pinfunction "XO_8") (pintype "passive"))
      (node (ref "Y1") (pin "1") (pinfunction "OSC1_1") (pintype "passive"))
    )
    (net (code "143") (name "Net-(U3-OSC_IN)") (class "Default")
      (node (ref "C24") (pin "1") (pinfunction "1_1") (pintype "passive"))
      (node (ref "R23") (pin "2") (pinfunction "2_2") (pintype "passive"))
      (node (ref "U3") (pin "23") (pinfunction "OSC_IN_23") (pintype "passive"))
      (node (ref "X2") (pin "1") (pinfunction "1_1") (pintype "passive"))
    )
    (net (code "144") (name "Net-(U3-OSC_OUT)") (class "Default")
      (node (ref "C27") (pin "1") (pinfunction "1_1") (pintype "passive"))
      (node (ref "R23") (pin "1") (pinfunction "1_1") (pintype "passive"))
      (node (ref "U3") (pin "24") (pinfunction "OSC_OUT_24") (pintype "passive"))
      (node (ref "X2") (pin "2") (pinfunction "2_2") (pintype "passive"))
    )
    (net (code "145") (name "Net-(U3-VBAT)") (class "Default")
      (node (ref "R19") (pin "2") (pinfunction "2_2") (pintype "passive"))
      (node (ref "R22") (pin "2") (pinfunction "2_2") (pintype "passive"))
      (node (ref "U3") (pin "6") (pinfunction "VBAT_6") (pintype "passive"))
    )
    (net (code "146") (name "USB_VCC") (class "Default")
      (node (ref "K1") (pin "3") (pinfunction "I/O1_3") (pintype "passive"))
      (node (ref "USB_1") (pin "1") (pinfunction "VCC_1") (pintype "passive"))
    )
    (net (code "147") (name "VDDA") (class "Default")
      (node (ref "C5") (pin "1") (pinfunction "1_1") (pintype "passive"))
      (node (ref "L1") (pin "1") (pinfunction "1_1") (pintype "passive"))
      (node (ref "L2") (pin "2") (pinfunction "2_2") (pintype "passive"))
      (node (ref "P4") (pin "48") (pinfunction "48_48") (pintype "passive"))
      (node (ref "U3") (pin "33") (pinfunction "VDDA_33") (pintype "passive"))
    )
    (net (code "148") (name "VREF+") (class "Default")
      (node (ref "C6") (pin "1") (pinfunction "1_1") (pintype "passive"))
      (node (ref "C7") (pin "1") (pinfunction "1_1") (pintype "passive"))
      (node (ref "L2") (pin "1") (pinfunction "1_1") (pintype "passive"))
      (node (ref "P4") (pin "49") (pinfunction "49_49") (pintype "passive"))
      (node (ref "U3") (pin "32") (pinfunction "Vref+_32") (pintype "passive"))
    )
    (net (code "149") (name "VREF-") (class "Default")
      (node (ref "C6") (pin "2") (pinfunction "2_2") (pintype "passive"))
      (node (ref "C7") (pin "2") (pinfunction "2_2") (pintype "passive"))
      (node (ref "L4") (pin "1") (pinfunction "1_1") (pintype "passive"))
      (node (ref "P4") (pin "50") (pinfunction "50_50") (pintype "passive"))
      (node (ref "U3") (pin "31") (pinfunction "Vref-_31") (pintype "passive"))
    )
    (net (code "150") (name "VSSA") (class "Default")
      (node (ref "C5") (pin "2") (pinfunction "2_2") (pintype "passive"))
      (node (ref "L3") (pin "1") (pinfunction "1_1") (pintype "passive"))
      (node (ref "L4") (pin "2") (pinfunction "2_2") (pintype "passive"))
      (node (ref "P4") (pin "51") (pinfunction "51_51") (pintype "passive"))
      (node (ref "U3") (pin "30") (pinfunction "VSSA_30") (pintype "passive"))
    )
    (net (code "151") (name "unconnected-(J2-Pad17)") (class "Default")
      (node (ref "J2") (pin "17") (pinfunction "17_17") (pintype "passive"))
    )
    (net (code "152") (name "unconnected-(K1-I{slash}O1-Pad1)") (class "Default")
      (node (ref "K1") (pin "1") (pinfunction "I/O1_1") (pintype "passive"))
    )
    (net (code "153") (name "unconnected-(K1-I{slash}O2-Pad4)") (class "Default")
      (node (ref "K1") (pin "4") (pinfunction "I/O2_4") (pintype "passive"))
    )
    (net (code "154") (name "unconnected-(K1-I{slash}O2-Pad6)") (class "Default")
      (node (ref "K1") (pin "6") (pinfunction "I/O2_6") (pintype "passive"))
    )
    (net (code "155") (name "unconnected-(K1-TAP2-Pad5)") (class "Default")
      (node (ref "K1") (pin "5") (pinfunction "TAP2_5") (pintype "passive"))
    )
    (net (code "156") (name "unconnected-(U2-CTS#-Pad9)") (class "Default")
      (node (ref "U2") (pin "9") (pinfunction "CTS#_9") (pintype "passive"))
    )
    (net (code "157") (name "unconnected-(U2-DCD#-Pad12)") (class "Default")
      (node (ref "U2") (pin "12") (pinfunction "DCD#_12") (pintype "passive"))
    )
    (net (code "158") (name "unconnected-(U2-DSR#-Pad10)") (class "Default")
      (node (ref "U2") (pin "10") (pinfunction "DSR#_10") (pintype "passive"))
    )
    (net (code "159") (name "unconnected-(U2-R232-Pad15)") (class "Default")
      (node (ref "U2") (pin "15") (pinfunction "R232_15") (pintype "passive"))
    )
    (net (code "160") (name "unconnected-(U2-RI#-Pad11)") (class "Default")
      (node (ref "U2") (pin "11") (pinfunction "RI#_11") (pintype "passive"))
    )
    (net (code "161") (name "unconnected-(U3-NC-Pad106)") (class "Default")
      (node (ref "U3") (pin "106") (pinfunction "NC_106") (pintype "passive"))
    )
    (net (code "162") (name "unconnected-(USB_1-NC-Pad4)") (class "Default")
      (node (ref "USB_1") (pin "4") (pinfunction "NC_4") (pintype "passive+no_connect"))
    )
    (net (code "163") (name "unconnected-(X1-Pad2)") (class "Default")
      (node (ref "X1") (pin "2") (pinfunction "2_2") (pintype "passive"))
    )
    (net (code "164") (name "unconnected-(X1-Pad3)") (class "Default")
      (node (ref "X1") (pin "3") (pinfunction "3_3") (pintype "passive"))
    )
  )
)
